# 04_Temperature.net
KiCad netlist of a schematic drawn in Altium Designer
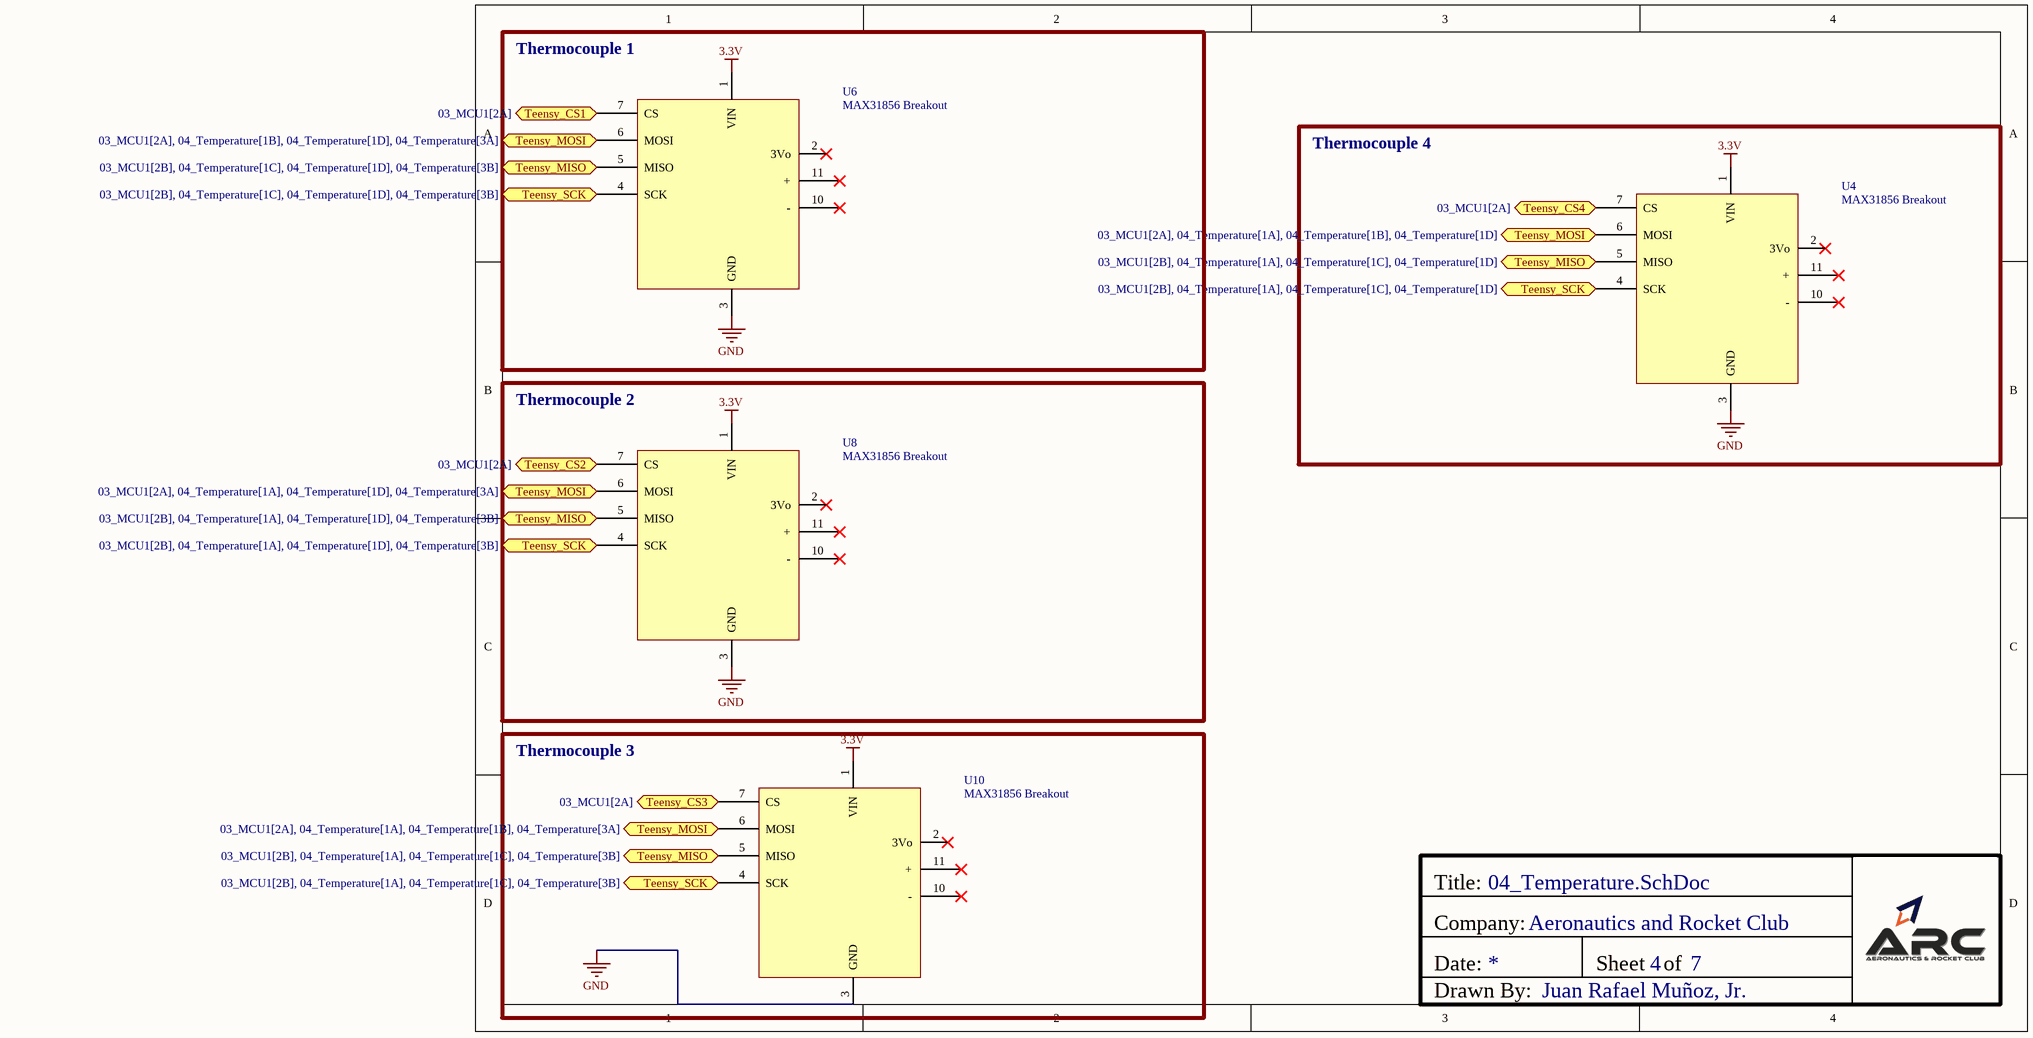
[diagram p0: 04_Temperature.SchDoc]

(export (version "E")
  (design (tool "Eeschema 10.0.6"))
  (components
    (comp (ref "U4")
      (value "MAX31856 Breakout")
      (footprint "MAX31856 Breakout")
      (libsource (lib "Ground Support_Schlib") (part "MAX31856 Breakout"))
    )
    (comp (ref "U6")
      (value "MAX31856 Breakout")
      (footprint "MAX31856 Breakout")
      (libsource (lib "Ground Support_Schlib") (part "MAX31856 Breakout"))
    )
    (comp (ref "U8")
      (value "MAX31856 Breakout")
      (footprint "MAX31856 Breakout")
      (libsource (lib "Ground Support_Schlib") (part "MAX31856 Breakout"))
    )
    (comp (ref "U10")
      (value "MAX31856 Breakout")
      (footprint "MAX31856 Breakout")
      (libsource (lib "Ground Support_Schlib") (part "MAX31856 Breakout"))
    )
  )
  (nets
    (net (code "1") (name "/Teensy_CS1") (class "Default")
      (node (ref "U6") (pin "7") (pinfunction "CS_7") (pintype "passive"))
    )
    (net (code "2") (name "/Teensy_CS2") (class "Default")
      (node (ref "U8") (pin "7") (pinfunction "CS_7") (pintype "passive"))
    )
    (net (code "3") (name "/Teensy_CS3") (class "Default")
      (node (ref "U10") (pin "7") (pinfunction "CS_7") (pintype "passive"))
    )
    (net (code "4") (name "/Teensy_CS4") (class "Default")
      (node (ref "U4") (pin "7") (pinfunction "CS_7") (pintype "passive"))
    )
    (net (code "5") (name "/Teensy_MISO") (class "Default")
      (node (ref "U10") (pin "5") (pinfunction "MISO_5") (pintype "passive"))
      (node (ref "U4") (pin "5") (pinfunction "MISO_5") (pintype "passive"))
      (node (ref "U6") (pin "5") (pinfunction "MISO_5") (pintype "passive"))
      (node (ref "U8") (pin "5") (pinfunction "MISO_5") (pintype "passive"))
    )
    (net (code "6") (name "/Teensy_MOSI") (class "Default")
      (node (ref "U10") (pin "6") (pinfunction "MOSI_6") (pintype "passive"))
      (node (ref "U4") (pin "6") (pinfunction "MOSI_6") (pintype "passive"))
      (node (ref "U6") (pin "6") (pinfunction "MOSI_6") (pintype "passive"))
      (node (ref "U8") (pin "6") (pinfunction "MOSI_6") (pintype "passive"))
    )
    (net (code "7") (name "/Teensy_SCK") (class "Default")
      (node (ref "U10") (pin "4") (pinfunction "SCK_4") (pintype "passive"))
      (node (ref "U4") (pin "4") (pinfunction "SCK_4") (pintype "passive"))
      (node (ref "U6") (pin "4") (pinfunction "SCK_4") (pintype "passive"))
      (node (ref "U8") (pin "4") (pinfunction "SCK_4") (pintype "passive"))
    )
    (net (code "8") (name "3.3V") (class "Default")
      (node (ref "U10") (pin "1") (pinfunction "VIN_1") (pintype "passive"))
      (node (ref "U4") (pin "1") (pinfunction "VIN_1") (pintype "passive"))
      (node (ref "U6") (pin "1") (pinfunction "VIN_1") (pintype "passive"))
      (node (ref "U8") (pin "1") (pinfunction "VIN_1") (pintype "passive"))
    )
    (net (code "9") (name "GND") (class "Default")
      (node (ref "U10") (pin "3") (pinfunction "GND_3") (pintype "passive"))
      (node (ref "U4") (pin "3") (pinfunction "GND_3") (pintype "passive"))
      (node (ref "U6") (pin "3") (pinfunction "GND_3") (pintype "passive"))
      (node (ref "U8") (pin "3") (pinfunction "GND_3") (pintype "passive"))
    )
    (net (code "10") (name "unconnected-(U4-+-Pad11)") (class "Default")
      (node (ref "U4") (pin "11") (pinfunction "+_11") (pintype "passive+no_connect"))
    )
    (net (code "11") (name "unconnected-(U4---Pad10)") (class "Default")
      (node (ref "U4") (pin "10") (pinfunction "-_10") (pintype "passive+no_connect"))
    )
    (net (code "12") (name "unconnected-(U4-3Vo-Pad2)") (class "Default")
      (node (ref "U4") (pin "2") (pinfunction "3Vo_2") (pintype "passive+no_connect"))
    )
    (net (code "13") (name "unconnected-(U6-+-Pad11)") (class "Default")
      (node (ref "U6") (pin "11") (pinfunction "+_11") (pintype "passive+no_connect"))
    )
    (net (code "14") (name "unconnected-(U6---Pad10)") (class "Default")
      (node (ref "U6") (pin "10") (pinfunction "-_10") (pintype "passive+no_connect"))
    )
    (net (code "15") (name "unconnected-(U6-3Vo-Pad2)") (class "Default")
      (node (ref "U6") (pin "2") (pinfunction "3Vo_2") (pintype "passive+no_connect"))
    )
    (net (code "16") (name "unconnected-(U8-+-Pad11)") (class "Default")
      (node (ref "U8") (pin "11") (pinfunction "+_11") (pintype "passive+no_connect"))
    )
    (net (code "17") (name "unconnected-(U8---Pad10)") (class "Default")
      (node (ref "U8") (pin "10") (pinfunction "-_10") (pintype "passive+no_connect"))
    )
    (net (code "18") (name "unconnected-(U8-3Vo-Pad2)") (class "Default")
      (node (ref "U8") (pin "2") (pinfunction "3Vo_2") (pintype "passive+no_connect"))
    )
    (net (code "19") (name "unconnected-(U10-+-Pad11)") (class "Default")
      (node (ref "U10") (pin "11") (pinfunction "+_11") (pintype "passive+no_connect"))
    )
    (net (code "20") (name "unconnected-(U10---Pad10)") (class "Default")
      (node (ref "U10") (pin "10") (pinfunction "-_10") (pintype "passive+no_connect"))
    )
    (net (code "21") (name "unconnected-(U10-3Vo-Pad2)") (class "Default")
      (node (ref "U10") (pin "2") (pinfunction "3Vo_2") (pintype "passive+no_connect"))
    )
  )
)
